# smartdim.net
KiCad netlist of a schematic drawn in EAGLE
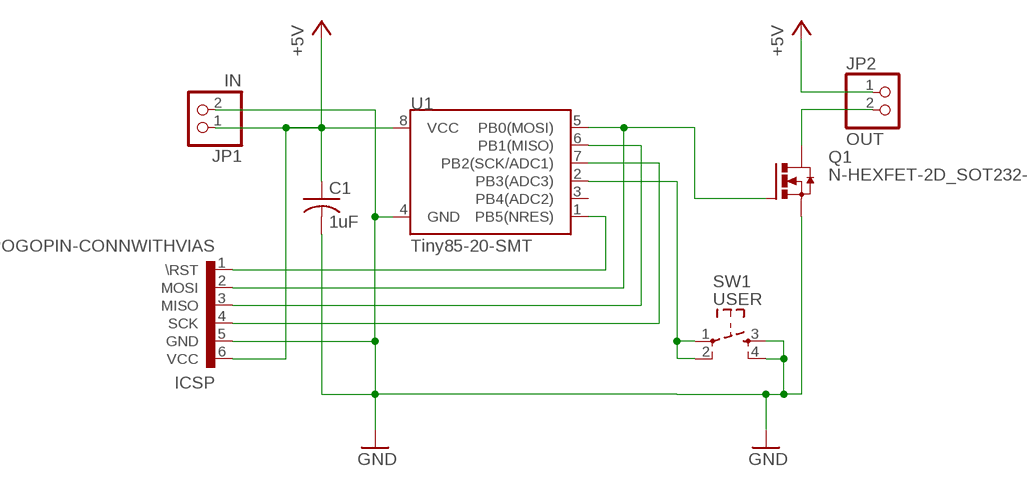
[diagram p0: schematic, sheet 1]

(export (version "E")
  (design (tool "Eeschema 10.0.6"))
  (components
    (comp (ref "C1")
      (value "1uF")
      (footprint "eagle-import:C0805")
      (libsource (lib "eagle-import") (part "C-USC0805"))
    )
    (comp (ref "ICSP")
      (value "POGOPIN-CONNWITHVIAS")
      (footprint "eagle-import:POGOPROG-CONN-0H")
      (libsource (lib "eagle-import") (part "POGOPIN-CONNWITHVIAS"))
    )
    (comp (ref "JP1")
      (value "IN")
      (footprint "eagle-import:1X02")
      (libsource (lib "eagle-import") (part "PINHD-1X2"))
    )
    (comp (ref "JP2")
      (value "OUT")
      (footprint "eagle-import:1X02")
      (libsource (lib "eagle-import") (part "PINHD-1X2"))
    )
    (comp (ref "Q1")
      (value "N-HEXFET-2D_SOT232-")
      (footprint "eagle-import:SOT223")
      (libsource (lib "eagle-import") (part "N-HEXFET-2D_?-SOT232"))
    )
    (comp (ref "SW1")
      (value "USER")
      (footprint "eagle-import:SW_TACT_SMALL")
      (libsource (lib "eagle-import") (part "SW_TACT_4P"))
    )
    (comp (ref "U1")
      (value "Tiny85-20-SMT")
      (footprint "eagle-import:SO08-EIAJ")
      (libsource (lib "eagle-import") (part "ATTINY45TINY85-20-SMT"))
    )
  )
  (nets
    (net (code "1") (name "+5V") (class "Default")
      (node (ref "C1") (pin "1") (pinfunction "1_1") (pintype "passive"))
      (node (ref "ICSP") (pin "6") (pinfunction "VCC_6") (pintype "bidirectional"))
      (node (ref "JP1") (pin "1") (pinfunction "1_1") (pintype "passive"))
      (node (ref "JP2") (pin "1") (pinfunction "1_1") (pintype "passive"))
      (node (ref "U1") (pin "8") (pinfunction "VCC_8") (pintype "bidirectional"))
    )
    (net (code "2") (name "GND") (class "Default")
      (node (ref "C1") (pin "2") (pinfunction "2_2") (pintype "passive"))
      (node (ref "ICSP") (pin "5") (pinfunction "GND_5") (pintype "bidirectional"))
      (node (ref "JP1") (pin "2") (pinfunction "2_2") (pintype "passive"))
      (node (ref "Q1") (pin "3") (pinfunction "S_3") (pintype "passive"))
      (node (ref "SW1") (pin "3") (pinfunction "3_3") (pintype "passive"))
      (node (ref "SW1") (pin "4") (pinfunction "4_4") (pintype "passive"))
      (node (ref "U1") (pin "4") (pinfunction "GND_4") (pintype "bidirectional"))
    )
    (net (code "3") (name "Net-(ICSP-MISO)") (class "Default")
      (node (ref "ICSP") (pin "3") (pinfunction "MISO_3") (pintype "bidirectional"))
      (node (ref "U1") (pin "6") (pinfunction "PB1(MISO)_6") (pintype "bidirectional"))
    )
    (net (code "4") (name "Net-(ICSP-MOSI)") (class "Default")
      (node (ref "ICSP") (pin "2") (pinfunction "MOSI_2") (pintype "bidirectional"))
      (node (ref "Q1") (pin "1") (pinfunction "G_1") (pintype "passive"))
      (node (ref "U1") (pin "5") (pinfunction "PB0(MOSI)_5") (pintype "bidirectional"))
    )
    (net (code "5") (name "Net-(ICSP-SCK)") (class "Default")
      (node (ref "ICSP") (pin "4") (pinfunction "SCK_4") (pintype "bidirectional"))
      (node (ref "U1") (pin "7") (pinfunction "PB2(SCK/ADC1)_7") (pintype "bidirectional"))
    )
    (net (code "6") (name "Net-(ICSP-\\RST)") (class "Default")
      (node (ref "ICSP") (pin "1") (pinfunction "\\RST_1") (pintype "bidirectional"))
      (node (ref "U1") (pin "1") (pinfunction "PB5(NRES)_1") (pintype "bidirectional"))
    )
    (net (code "7") (name "Net-(JP2-Pad2)") (class "Default")
      (node (ref "JP2") (pin "2") (pinfunction "2_2") (pintype "passive"))
      (node (ref "Q1") (pin "2") (pinfunction "D_2") (pintype "passive"))
      (node (ref "Q1") (pin "4") (pinfunction "D_4") (pintype "passive"))
    )
    (net (code "8") (name "Net-(U1-PB3(ADC3))") (class "Default")
      (node (ref "SW1") (pin "1") (pinfunction "1_1") (pintype "passive"))
      (node (ref "SW1") (pin "2") (pinfunction "2_2") (pintype "passive"))
      (node (ref "U1") (pin "2") (pinfunction "PB3(ADC3)_2") (pintype "bidirectional"))
    )
    (net (code "9") (name "unconnected-(U1-PB4(ADC2)-Pad3)") (class "Default")
      (node (ref "U1") (pin "3") (pinfunction "PB4(ADC2)_3") (pintype "bidirectional"))
    )
  )
)
